# HallSensor.net
KiCad netlist of a schematic drawn in Altium Designer
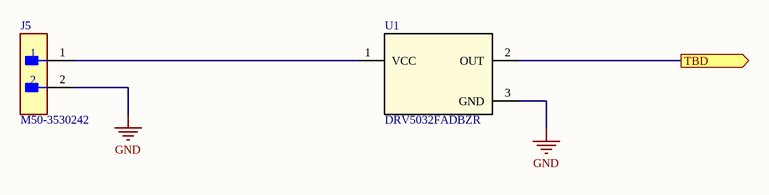
[diagram p0: HallSensor.SchDoc]

(export (version "E")
  (design (tool "Eeschema 10.0.6"))
  (components
    (comp (ref "J5")
      (value "M50-3530242")
      (footprint "FP-M50-3530242-MFG")
      (description "CONN HEADER VERT 2POS 1.27MM")
      (libsource (lib "Altium Content Vault") (part "3bc925449376181038e59eaffc5286c"))
    )
    (comp (ref "U1")
      (value "DRV5032FADBZR")
      (footprint "DBZ0003A-IPC_A")
      (description "Low-power (5Hz, <1ÂµA) low-voltage (up to 5.5V) switch 3-SOT-23 -40 to 85")
      (fields (field (name "COPYRIGHT") "Copyright (C) 2026 Ultra Librarian. All rights reserved."))
      (libsource (lib "DRV5032FADBZR") (part "DRV5032FADBZR"))
    )
  )
  (nets
    (net (code "1") (name "/TBD") (class "Default")
      (node (ref "U1") (pin "2") (pinfunction "OUT_2") (pintype "open_collector"))
    )
    (net (code "2") (name "GND") (class "Default")
      (node (ref "J5") (pin "2") (pinfunction "2_2") (pintype "passive"))
      (node (ref "U1") (pin "3") (pinfunction "GND_3") (pintype "power_in"))
    )
    (net (code "3") (name "Net-(U1-VCC)") (class "Default")
      (node (ref "J5") (pin "1") (pinfunction "1_1") (pintype "passive"))
      (node (ref "U1") (pin "1") (pinfunction "VCC_1") (pintype "power_in"))
    )
  )
)
